# MQTT_Wifi_GW.net
KiCad netlist of a schematic drawn in EAGLE
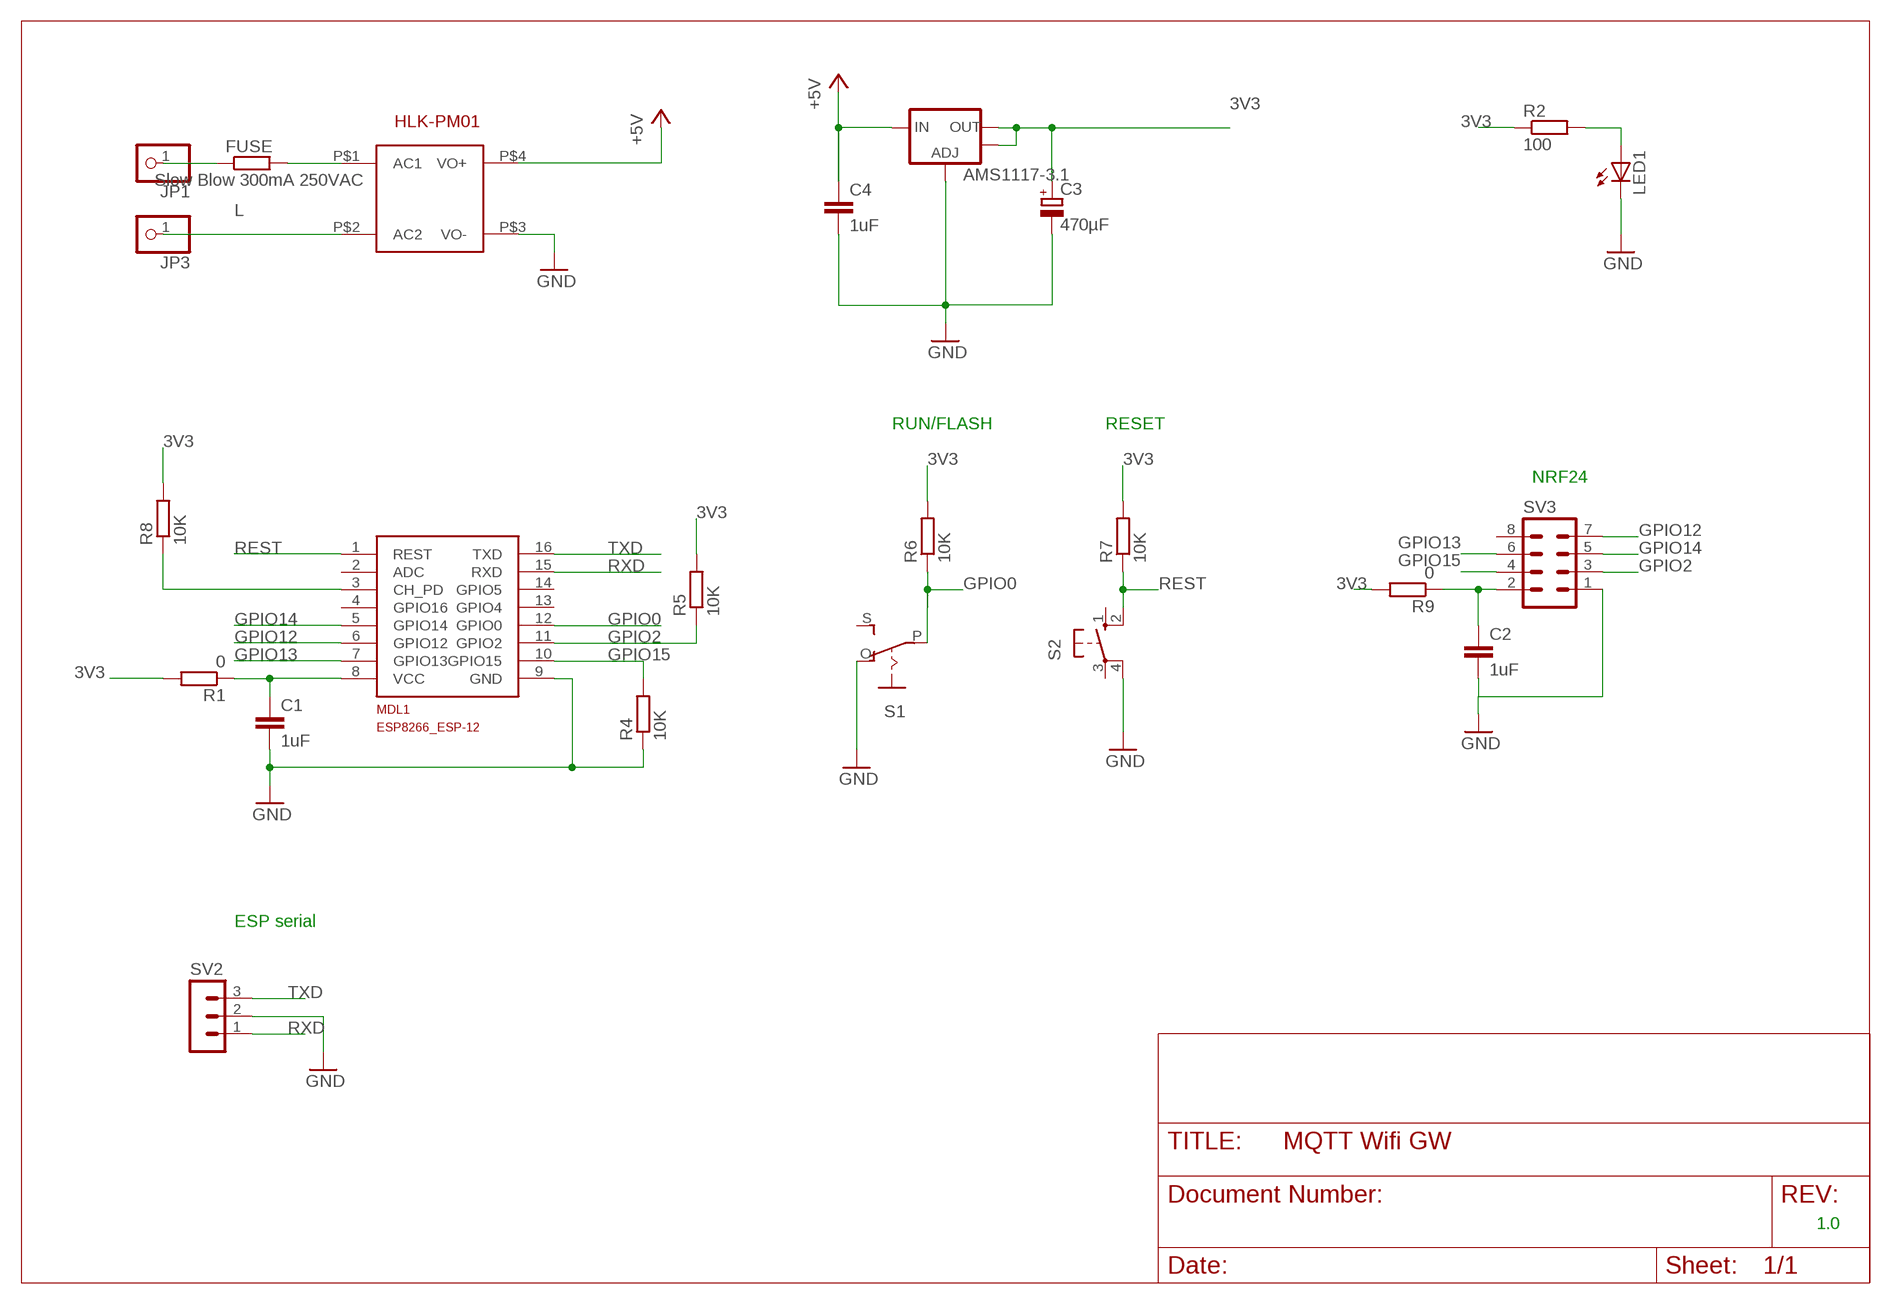
[diagram p0: schematic, sheet 1]

(export (version "E")
  (design (tool "Eeschema 10.0.6"))
  (components
    (comp (ref "AMS1117-3.1")
      (value "V_REG_LM1117SOT223")
      (footprint "eagle-import:SOT223")
      (libsource (lib "eagle-import") (part "V_REG_LM1117SOT223"))
    )
    (comp (ref "C1")
      (value "1uF")
      (footprint "eagle-import:C1206K")
      (libsource (lib "eagle-import") (part "C-EUC1206K"))
    )
    (comp (ref "C2")
      (value "1uF")
      (footprint "eagle-import:C1206K")
      (libsource (lib "eagle-import") (part "C-EUC1206K"))
    )
    (comp (ref "C3")
      (value "470µF")
      (footprint "eagle-import:E5-8,5")
      (libsource (lib "eagle-import") (part "CPOL-EUE5-8.5"))
    )
    (comp (ref "C4")
      (value "1uF")
      (footprint "eagle-import:C1206K")
      (libsource (lib "eagle-import") (part "C-EUC1206K"))
    )
    (comp (ref "FUSE")
      (value "Slow Blow 300mA 250VAC")
      (footprint "eagle-import:0411V")
      (libsource (lib "eagle-import") (part "R-EU_0411/3V"))
    )
    (comp (ref "HLK-PM01")
      (value "HLK-PM01")
      (footprint "eagle-import:HLK-PM01")
      (libsource (lib "eagle-import") (part "HLK-PM01"))
    )
    (comp (ref "JP1")
      (value "PINHD-1X1")
      (footprint "eagle-import:1X01")
      (libsource (lib "eagle-import") (part "PINHD-1X1"))
    )
    (comp (ref "JP3")
      (value "PINHD-1X1")
      (footprint "eagle-import:1X01")
      (libsource (lib "eagle-import") (part "PINHD-1X1"))
    )
    (comp (ref "LED1")
      (value "LED5MM")
      (footprint "eagle-import:LED5MM")
      (libsource (lib "eagle-import") (part "LED5MM"))
    )
    (comp (ref "MDL1")
      (value "ESP8266-12GPIO04/05_CORRECTED")
      (footprint "eagle-import:ESP8266-ESP12")
      (libsource (lib "eagle-import") (part "ESP8266-12GPIO04/05_CORRECTED"))
    )
    (comp (ref "R1")
      (value "0")
      (footprint "eagle-import:R0805")
      (libsource (lib "eagle-import") (part "resistor_R-EU_R0805"))
    )
    (comp (ref "R2")
      (value "100")
      (footprint "eagle-import:0207_10")
      (libsource (lib "eagle-import") (part "R-EU_0207/10"))
    )
    (comp (ref "R4")
      (value "10K")
      (footprint "eagle-import:R0805")
      (libsource (lib "eagle-import") (part "resistor_R-EU_R0805"))
    )
    (comp (ref "R5")
      (value "10K")
      (footprint "eagle-import:R0805")
      (libsource (lib "eagle-import") (part "resistor_R-EU_R0805"))
    )
    (comp (ref "R6")
      (value "10K")
      (footprint "eagle-import:R0805")
      (libsource (lib "eagle-import") (part "resistor_R-EU_R0805"))
    )
    (comp (ref "R7")
      (value "10K")
      (footprint "eagle-import:R0805")
      (libsource (lib "eagle-import") (part "resistor_R-EU_R0805"))
    )
    (comp (ref "R8")
      (value "10K")
      (footprint "eagle-import:R1206")
      (libsource (lib "eagle-import") (part "resistor_R-EU_R1206"))
    )
    (comp (ref "R9")
      (value "0")
      (footprint "eagle-import:R1206")
      (libsource (lib "eagle-import") (part "resistor_R-EU_R1206"))
    )
    (comp (ref "S1")
      (value "EG1218S")
      (footprint "eagle-import:EG1218")
      (libsource (lib "eagle-import") (part "EG1218S"))
    )
    (comp (ref "S2")
      (value "10-XX")
      (footprint "eagle-import:B3F-10XX")
      (fields (field (name "MPN") "B3F-1000"))
      (libsource (lib "eagle-import") (part "10-XX"))
    )
    (comp (ref "SV2")
      (value "MA03-1")
      (footprint "eagle-import:MA03-1")
      (libsource (lib "eagle-import") (part "MA03-1"))
    )
    (comp (ref "SV3")
      (value "MA04-2")
      (footprint "eagle-import:MA04-2")
      (libsource (lib "eagle-import") (part "MA04-2"))
    )
  )
  (nets
    (net (code "1") (name "+5V") (class "Default")
      (node (ref "AMS1117-3.1") (pin "3") (pinfunction "IN_3") (pintype "input"))
      (node (ref "C4") (pin "1") (pinfunction "1_1") (pintype "passive"))
      (node (ref "HLK-PM01") (pin "P$4") (pinfunction "VO+_P$4") (pintype "power_in"))
    )
    (net (code "2") (name "/3V3") (class "Default")
      (node (ref "AMS1117-3.1") (pin "2") (pinfunction "OUT_2") (pintype "output"))
      (node (ref "AMS1117-3.1") (pin "4") (pinfunction "OUT_4") (pintype "output"))
      (node (ref "C3") (pin "+") (pinfunction "+_+") (pintype "passive"))
      (node (ref "R1") (pin "2") (pinfunction "2_2") (pintype "passive"))
      (node (ref "R2") (pin "1") (pinfunction "1_1") (pintype "passive"))
      (node (ref "R5") (pin "2") (pinfunction "2_2") (pintype "passive"))
      (node (ref "R6") (pin "2") (pinfunction "2_2") (pintype "passive"))
      (node (ref "R7") (pin "2") (pinfunction "2_2") (pintype "passive"))
      (node (ref "R8") (pin "2") (pinfunction "2_2") (pintype "passive"))
      (node (ref "R9") (pin "2") (pinfunction "2_2") (pintype "passive"))
    )
    (net (code "3") (name "/GPIO0") (class "Default")
      (node (ref "MDL1") (pin "12") (pinfunction "GPIO0_12") (pintype "bidirectional"))
      (node (ref "R6") (pin "1") (pinfunction "1_1") (pintype "passive"))
      (node (ref "S1") (pin "P") (pinfunction "P_P") (pintype "passive"))
    )
    (net (code "4") (name "/GPIO2") (class "Default")
      (node (ref "MDL1") (pin "11") (pinfunction "GPIO2_11") (pintype "bidirectional"))
      (node (ref "R5") (pin "1") (pinfunction "1_1") (pintype "passive"))
      (node (ref "SV3") (pin "3") (pinfunction "3_3") (pintype "passive"))
    )
    (net (code "5") (name "/GPIO12") (class "Default")
      (node (ref "MDL1") (pin "6") (pinfunction "GPIO12_6") (pintype "bidirectional"))
      (node (ref "SV3") (pin "7") (pinfunction "7_7") (pintype "passive"))
    )
    (net (code "6") (name "/GPIO13") (class "Default")
      (node (ref "MDL1") (pin "7") (pinfunction "GPIO13_7") (pintype "bidirectional"))
      (node (ref "SV3") (pin "6") (pinfunction "6_6") (pintype "passive"))
    )
    (net (code "7") (name "/GPIO14") (class "Default")
      (node (ref "MDL1") (pin "5") (pinfunction "GPIO14_5") (pintype "bidirectional"))
      (node (ref "SV3") (pin "5") (pinfunction "5_5") (pintype "passive"))
    )
    (net (code "8") (name "/GPIO15") (class "Default")
      (node (ref "MDL1") (pin "10") (pinfunction "GPIO15_10") (pintype "bidirectional"))
      (node (ref "R4") (pin "2") (pinfunction "2_2") (pintype "passive"))
      (node (ref "SV3") (pin "4") (pinfunction "4_4") (pintype "passive"))
    )
    (net (code "9") (name "/L") (class "Default")
      (node (ref "HLK-PM01") (pin "P$2") (pinfunction "AC2_P$2") (pintype "input"))
      (node (ref "JP3") (pin "1") (pinfunction "1_1") (pintype "passive"))
    )
    (net (code "10") (name "/REST") (class "Default")
      (node (ref "MDL1") (pin "1") (pinfunction "REST_1") (pintype "bidirectional"))
      (node (ref "R7") (pin "1") (pinfunction "1_1") (pintype "passive"))
      (node (ref "S2") (pin "2") (pinfunction "S1_2") (pintype "passive"))
    )
    (net (code "11") (name "/RXD") (class "Default")
      (node (ref "MDL1") (pin "15") (pinfunction "RXD_15") (pintype "bidirectional"))
      (node (ref "SV2") (pin "1") (pinfunction "1_1") (pintype "passive"))
    )
    (net (code "12") (name "/TXD") (class "Default")
      (node (ref "MDL1") (pin "16") (pinfunction "TXD_16") (pintype "bidirectional"))
      (node (ref "SV2") (pin "3") (pinfunction "3_3") (pintype "passive"))
    )
    (net (code "13") (name "GND") (class "Default")
      (node (ref "AMS1117-3.1") (pin "1") (pinfunction "ADJ_1") (pintype "input"))
      (node (ref "C1") (pin "2") (pinfunction "2_2") (pintype "passive"))
      (node (ref "C2") (pin "2") (pinfunction "2_2") (pintype "passive"))
      (node (ref "C3") (pin "-") (pinfunction "-_-") (pintype "passive"))
      (node (ref "C4") (pin "2") (pinfunction "2_2") (pintype "passive"))
      (node (ref "HLK-PM01") (pin "P$3") (pinfunction "VO-_P$3") (pintype "power_in"))
      (node (ref "LED1") (pin "K") (pinfunction "C_K") (pintype "passive"))
      (node (ref "MDL1") (pin "9") (pinfunction "GND_9") (pintype "bidirectional"))
      (node (ref "R4") (pin "1") (pinfunction "1_1") (pintype "passive"))
      (node (ref "S1") (pin "O") (pinfunction "O_O") (pintype "passive"))
      (node (ref "S2") (pin "4") (pinfunction "P1_4") (pintype "passive"))
      (node (ref "SV2") (pin "2") (pinfunction "2_2") (pintype "passive"))
      (node (ref "SV3") (pin "1") (pinfunction "1_1") (pintype "passive"))
    )
    (net (code "14") (name "Net-(C2-Pad1)") (class "Default")
      (node (ref "C2") (pin "1") (pinfunction "1_1") (pintype "passive"))
      (node (ref "R9") (pin "1") (pinfunction "1_1") (pintype "passive"))
      (node (ref "SV3") (pin "2") (pinfunction "2_2") (pintype "passive"))
    )
    (net (code "15") (name "Net-(FUSE-Pad1)") (class "Default")
      (node (ref "FUSE") (pin "1") (pinfunction "1_1") (pintype "passive"))
      (node (ref "JP1") (pin "1") (pinfunction "1_1") (pintype "passive"))
    )
    (net (code "16") (name "Net-(HLK-PM01-AC1)") (class "Default")
      (node (ref "FUSE") (pin "2") (pinfunction "2_2") (pintype "passive"))
      (node (ref "HLK-PM01") (pin "P$1") (pinfunction "AC1_P$1") (pintype "input"))
    )
    (net (code "17") (name "Net-(LED1-PadA)") (class "Default")
      (node (ref "LED1") (pin "A") (pinfunction "A_A") (pintype "passive"))
      (node (ref "R2") (pin "2") (pinfunction "2_2") (pintype "passive"))
    )
    (net (code "18") (name "Net-(MDL1-CH_PD)") (class "Default")
      (node (ref "MDL1") (pin "3") (pinfunction "CH_PD_3") (pintype "bidirectional"))
      (node (ref "R8") (pin "1") (pinfunction "1_1") (pintype "passive"))
    )
    (net (code "19") (name "Net-(MDL1-VCC)") (class "Default")
      (node (ref "C1") (pin "1") (pinfunction "1_1") (pintype "passive"))
      (node (ref "MDL1") (pin "8") (pinfunction "VCC_8") (pintype "bidirectional"))
      (node (ref "R1") (pin "1") (pinfunction "1_1") (pintype "passive"))
    )
    (net (code "20") (name "unconnected-(MDL1-ADC-Pad2)") (class "Default")
      (node (ref "MDL1") (pin "2") (pinfunction "ADC_2") (pintype "bidirectional"))
    )
    (net (code "21") (name "unconnected-(MDL1-GPIO4-Pad13)") (class "Default")
      (node (ref "MDL1") (pin "13") (pinfunction "GPIO4_13") (pintype "bidirectional"))
    )
    (net (code "22") (name "unconnected-(MDL1-GPIO5-Pad14)") (class "Default")
      (node (ref "MDL1") (pin "14") (pinfunction "GPIO5_14") (pintype "bidirectional"))
    )
    (net (code "23") (name "unconnected-(MDL1-GPIO16-Pad4)") (class "Default")
      (node (ref "MDL1") (pin "4") (pinfunction "GPIO16_4") (pintype "bidirectional"))
    )
    (net (code "24") (name "unconnected-(S1-PadS)") (class "Default")
      (node (ref "S1") (pin "S") (pinfunction "S_S") (pintype "passive"))
    )
    (net (code "25") (name "unconnected-(S2-P-Pad3)") (class "Default")
      (node (ref "S2") (pin "3") (pinfunction "P_3") (pintype "passive"))
    )
    (net (code "26") (name "unconnected-(S2-S-Pad1)") (class "Default")
      (node (ref "S2") (pin "1") (pinfunction "S_1") (pintype "passive"))
    )
    (net (code "27") (name "unconnected-(SV3-Pad8)") (class "Default")
      (node (ref "SV3") (pin "8") (pinfunction "8_8") (pintype "passive"))
    )
  )
)
